# dsPIC.net
KiCad netlist of a schematic drawn in Altium Designer
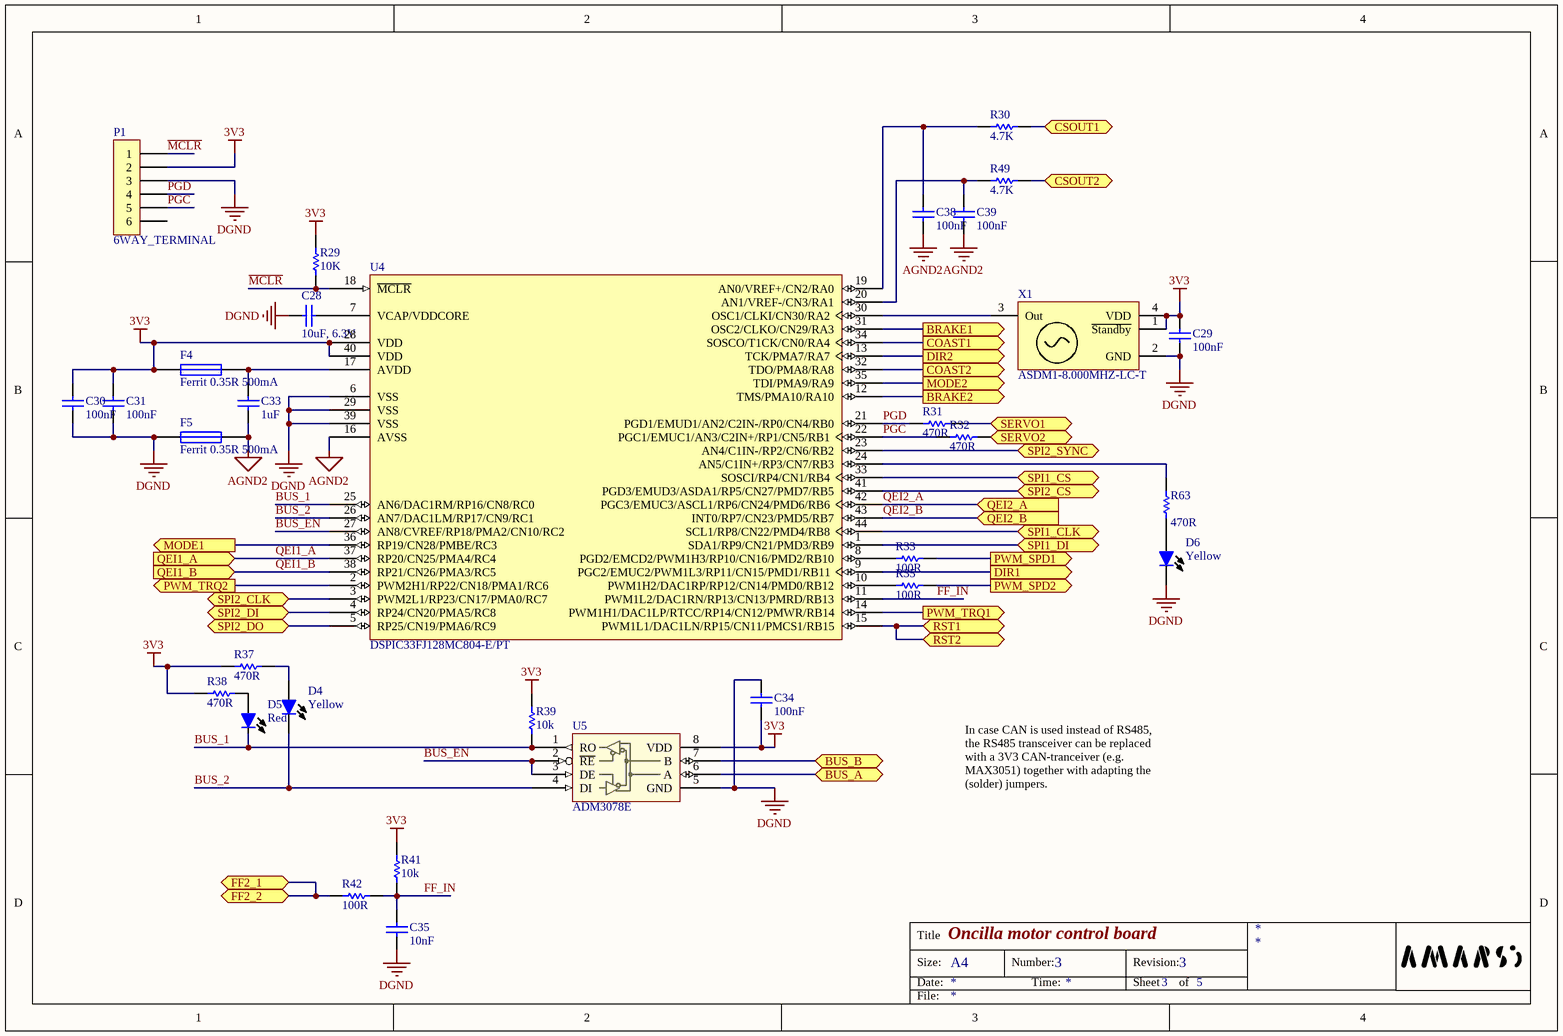
[diagram p0: dsPIC.SchDoc]

(export (version "E")
  (design (tool "Eeschema 10.0.6"))
  (components
    (comp (ref "C28")
      (value "10uF, 6.3V")
      (footprint "CAPC1608L")
      (description "Capacitor (Semiconductor SIM Model)")
      (fields (field (name "PUBLISHER") "Altium Limited"))
      (libsource (lib "Miscellaneous Devices") (part "Cap Semi"))
    )
    (comp (ref "C29")
      (value "100nF")
      (footprint "CAPC1608L")
      (description "Capacitor (Semiconductor SIM Model)")
      (fields (field (name "PUBLISHER") "Altium Limited"))
      (libsource (lib "Miscellaneous Devices") (part "Cap Semi"))
    )
    (comp (ref "C30")
      (value "100nF")
      (footprint "CAPC1608L")
      (description "Capacitor (Semiconductor SIM Model)")
      (fields (field (name "PUBLISHER") "Altium Limited"))
      (libsource (lib "Miscellaneous Devices") (part "Cap Semi"))
    )
    (comp (ref "C31")
      (value "100nF")
      (footprint "CAPC1608L")
      (description "Capacitor (Semiconductor SIM Model)")
      (fields (field (name "PUBLISHER") "Altium Limited"))
      (libsource (lib "Miscellaneous Devices") (part "Cap Semi"))
    )
    (comp (ref "C33")
      (value "1uF")
      (footprint "CAPC1608L")
      (description "Capacitor (Semiconductor SIM Model)")
      (fields (field (name "Comment") "1uF, 25V") (field (name "PUBLISHER") "Altium Limited"))
      (libsource (lib "Miscellaneous Devices") (part "Cap Semi"))
    )
    (comp (ref "C34")
      (value "100nF")
      (footprint "CAPC1608L")
      (description "Capacitor (Semiconductor SIM Model)")
      (fields (field (name "PUBLISHER") "Altium Limited"))
      (libsource (lib "Miscellaneous Devices") (part "Cap Semi"))
    )
    (comp (ref "C35")
      (value "10nF")
      (footprint "CAPC1608L")
      (description "Capacitor (Semiconductor SIM Model)")
      (fields (field (name "PUBLISHER") "Altium Limited"))
      (libsource (lib "Miscellaneous Devices") (part "Cap Semi"))
    )
    (comp (ref "C38")
      (value "100nF")
      (footprint "CAPC1608L")
      (description "Capacitor (Semiconductor SIM Model)")
      (fields (field (name "PUBLISHER") "Altium Limited"))
      (libsource (lib "Miscellaneous Devices") (part "Cap Semi"))
    )
    (comp (ref "C39")
      (value "100nF")
      (footprint "CAPC1608L")
      (description "Capacitor (Semiconductor SIM Model)")
      (fields (field (name "PUBLISHER") "Altium Limited"))
      (libsource (lib "Miscellaneous Devices") (part "Cap Semi"))
    )
    (comp (ref "D4")
      (value "LED Yellow")
      (footprint "CD1608-0603")
      (description "LED")
      (fields (field (name "COLOR") "Yellow"))
      (libsource (lib "Roombots") (part "LED"))
    )
    (comp (ref "D5")
      (value "LED Red")
      (footprint "CD1608-0603")
      (description "LED")
      (fields (field (name "COLOR") "Red"))
      (libsource (lib "Roombots") (part "LED"))
    )
    (comp (ref "D6")
      (value "LED Green")
      (footprint "CD1608-0603")
      (description "LED")
      (fields (field (name "COLOR") "Yellow"))
      (libsource (lib "Roombots") (part "LED"))
    )
    (comp (ref "F4")
      (value "Ferrit 0.35R 500mA")
      (footprint "RESC1608L")
      (description "Ferrit Bead")
      (fields (field (name "PUBLISHER") "Altium Limited"))
      (libsource (lib "Miscellaneous Devices") (part "Fuse 1"))
    )
    (comp (ref "F5")
      (value "Ferrit 0.35R 500mA")
      (footprint "RESC1608L")
      (description "Ferrit Bead")
      (fields (field (name "PUBLISHER") "Altium Limited"))
      (libsource (lib "Miscellaneous Devices") (part "Fuse 1"))
    )
    (comp (ref "P1")
      (value "6WAY_TERMINAL")
      (footprint "MICROMATCH_6WAY_SE")
      (libsource (lib "New_library") (part "6WAY_TERMINAL"))
    )
    (comp (ref "R29")
      (value "10K")
      (footprint "RESC1608L")
      (description "Semiconductor Resistor")
      (fields (field (name "Comment") "10k") (field (name "PUBLISHER") "Altium Limited"))
      (libsource (lib "Miscellaneous Devices") (part "Res Semi"))
    )
    (comp (ref "R30")
      (value "4.7K")
      (footprint "RESC1608L")
      (description "Semiconductor Resistor")
      (fields (field (name "Comment") "4.7k") (field (name "PUBLISHER") "Altium Limited"))
      (libsource (lib "Miscellaneous Devices") (part "Res Semi"))
    )
    (comp (ref "R31")
      (value "470R")
      (footprint "RESC1608L")
      (description "Semiconductor Resistor")
      (fields (field (name "PUBLISHER") "Altium Limited"))
      (libsource (lib "Miscellaneous Devices") (part "Res Semi"))
    )
    (comp (ref "R32")
      (value "470R")
      (footprint "RESC1608L")
      (description "Semiconductor Resistor")
      (fields (field (name "PUBLISHER") "Altium Limited"))
      (libsource (lib "Miscellaneous Devices") (part "Res Semi"))
    )
    (comp (ref "R33")
      (value "100R")
      (footprint "RESC1608L")
      (description "Semiconductor Resistor")
      (fields (field (name "PUBLISHER") "Altium Limited"))
      (libsource (lib "Miscellaneous Devices") (part "Res Semi"))
    )
    (comp (ref "R35")
      (value "100R")
      (footprint "RESC1608L")
      (description "Semiconductor Resistor")
      (fields (field (name "PUBLISHER") "Altium Limited"))
      (libsource (lib "Miscellaneous Devices") (part "Res Semi"))
    )
    (comp (ref "R37")
      (value "470R")
      (footprint "RESC1608L")
      (description "Semiconductor Resistor")
      (fields (field (name "PUBLISHER") "Altium Limited"))
      (libsource (lib "Miscellaneous Devices") (part "Res Semi"))
    )
    (comp (ref "R38")
      (value "470R")
      (footprint "RESC1608L")
      (description "Semiconductor Resistor")
      (fields (field (name "PUBLISHER") "Altium Limited"))
      (libsource (lib "Miscellaneous Devices") (part "Res Semi"))
    )
    (comp (ref "R39")
      (value "10k")
      (footprint "RESC1608L")
      (description "Semiconductor Resistor")
      (fields (field (name "PUBLISHER") "Altium Limited"))
      (libsource (lib "Miscellaneous Devices") (part "Res Semi"))
    )
    (comp (ref "R41")
      (value "10k")
      (footprint "RESC1608L")
      (description "Semiconductor Resistor")
      (fields (field (name "PUBLISHER") "Altium Limited"))
      (libsource (lib "Miscellaneous Devices") (part "Res Semi"))
    )
    (comp (ref "R42")
      (value "100R")
      (footprint "RESC1608L")
      (description "Semiconductor Resistor")
      (fields (field (name "PUBLISHER") "Altium Limited"))
      (libsource (lib "Miscellaneous Devices") (part "Res Semi"))
    )
    (comp (ref "R49")
      (value "4.7K")
      (footprint "RESC1608L")
      (description "Semiconductor Resistor")
      (fields (field (name "Comment") "4.7k") (field (name "PUBLISHER") "Altium Limited"))
      (libsource (lib "Miscellaneous Devices") (part "Res Semi"))
    )
    (comp (ref "R63")
      (value "470R")
      (footprint "RESC1608L")
      (description "Semiconductor Resistor")
      (fields (field (name "PUBLISHER") "Altium Limited"))
      (libsource (lib "Miscellaneous Devices") (part "Res Semi"))
    )
    (comp (ref "U4")
      (value "DSPIC33FJ128MC804-E/PT")
      (footprint "TQFP-PT44_N")
      (fields (field (name "PUBLISHER") "Altium Limited"))
      (libsource (lib "Microchip DSC 16-Bit dsPIC33F") (part "DSPIC33FJ128MC804-E/PT"))
    )
    (comp (ref "U5")
      (value "ADM3078E")
      (footprint "SOIC-8_M")
      (description "Half-Duplex RS485 Transciever, 3.3V, 16Mbps")
      (libsource (lib "Roombots") (part "ADM3078E"))
    )
    (comp (ref "X1")
      (value "ASDM1-8.000MHZ-LC-T")
      (footprint "Crystal-Oscillator-2520")
      (description "Oscillator")
      (libsource (lib "Roombots") (part "Oscillator"))
    )
  )
  (nets
    (net (code "1") (name "/BRAKE1") (class "Default")
      (node (ref "U4") (pin "31") (pinfunction "OSC2/CLKO/CN29/RA3_31") (pintype "bidirectional"))
    )
    (net (code "2") (name "/BRAKE2") (class "Default")
      (node (ref "U4") (pin "12") (pinfunction "TMS/PMA10/RA10_12") (pintype "bidirectional"))
    )
    (net (code "3") (name "/BUS_1") (class "Default")
      (node (ref "D5") (pin "2") (pinfunction "C_2") (pintype "passive"))
      (node (ref "R39") (pin "1") (pinfunction "1_1") (pintype "passive"))
      (node (ref "U4") (pin "25") (pinfunction "AN6/DAC1RM/RP16/CN8/RC0_25") (pintype "bidirectional"))
      (node (ref "U5") (pin "1") (pinfunction "RO_1") (pintype "output"))
    )
    (net (code "4") (name "/BUS_2") (class "Default")
      (node (ref "D4") (pin "2") (pinfunction "C_2") (pintype "passive"))
      (node (ref "U4") (pin "26") (pinfunction "AN7/DAC1LM/RP17/CN9/RC1_26") (pintype "bidirectional"))
      (node (ref "U5") (pin "4") (pinfunction "DI_4") (pintype "input"))
    )
    (net (code "5") (name "/BUS_A") (class "Default")
      (node (ref "U5") (pin "6") (pinfunction "A_6") (pintype "bidirectional"))
    )
    (net (code "6") (name "/BUS_B") (class "Default")
      (node (ref "U5") (pin "7") (pinfunction "B_7") (pintype "bidirectional"))
    )
    (net (code "7") (name "/BUS_EN") (class "Default")
      (node (ref "U4") (pin "27") (pinfunction "AN8/CVREF/RP18/PMA2/CN10/RC2_27") (pintype "bidirectional"))
      (node (ref "U5") (pin "2") (pinfunction "~{RE}_2") (pintype "input"))
      (node (ref "U5") (pin "3") (pinfunction "DE_3") (pintype "input"))
    )
    (net (code "8") (name "/COAST1") (class "Default")
      (node (ref "U4") (pin "34") (pinfunction "SOSCO/T1CK/CN0/RA4_34") (pintype "bidirectional"))
    )
    (net (code "9") (name "/COAST2") (class "Default")
      (node (ref "U4") (pin "32") (pinfunction "TDO/PMA8/RA8_32") (pintype "bidirectional"))
    )
    (net (code "10") (name "/CSOUT1") (class "Default")
      (node (ref "R30") (pin "2") (pinfunction "2_2") (pintype "passive"))
    )
    (net (code "11") (name "/CSOUT2") (class "Default")
      (node (ref "R49") (pin "2") (pinfunction "2_2") (pintype "passive"))
    )
    (net (code "12") (name "/DIR1") (class "Default")
      (node (ref "U4") (pin "9") (pinfunction "PGC2/EMUC2/PWM1L3/RP11/CN15/PMD1/RB11_9") (pintype "bidirectional"))
    )
    (net (code "13") (name "/DIR2") (class "Default")
      (node (ref "U4") (pin "13") (pinfunction "TCK/PMA7/RA7_13") (pintype "bidirectional"))
    )
    (net (code "14") (name "/FF2_1") (class "Default")
      (node (ref "R42") (pin "2") (pinfunction "2_2") (pintype "passive"))
    )
    (net (code "15") (name "/FF_IN") (class "Default")
      (node (ref "C35") (pin "2") (pinfunction "2_2") (pintype "passive"))
      (node (ref "R41") (pin "1") (pinfunction "1_1") (pintype "passive"))
      (node (ref "R42") (pin "1") (pinfunction "1_1") (pintype "passive"))
      (node (ref "U4") (pin "11") (pinfunction "PWM1L2/DAC1RN/RP13/CN13/PMRD/RB13_11") (pintype "bidirectional"))
    )
    (net (code "16") (name "/MODE1") (class "Default")
      (node (ref "U4") (pin "36") (pinfunction "RP19/CN28/PMBE/RC3_36") (pintype "bidirectional"))
    )
    (net (code "17") (name "/MODE2") (class "Default")
      (node (ref "U4") (pin "35") (pinfunction "TDI/PMA9/RA9_35") (pintype "bidirectional"))
    )
    (net (code "18") (name "/PGC") (class "Default")
      (node (ref "P1") (pin "5") (pinfunction "5_5") (pintype "passive"))
      (node (ref "R32") (pin "1") (pinfunction "1_1") (pintype "passive"))
      (node (ref "U4") (pin "22") (pinfunction "PGC1/EMUC1/AN3/C2IN+/RP1/CN5/RB1_22") (pintype "bidirectional"))
    )
    (net (code "19") (name "/PGD") (class "Default")
      (node (ref "P1") (pin "4") (pinfunction "4_4") (pintype "passive"))
      (node (ref "R31") (pin "1") (pinfunction "1_1") (pintype "passive"))
      (node (ref "U4") (pin "21") (pinfunction "PGD1/EMUD1/AN2/C2IN-/RP0/CN4/RB0_21") (pintype "bidirectional"))
    )
    (net (code "20") (name "/PWM_SPD1") (class "Default")
      (node (ref "R33") (pin "2") (pinfunction "2_2") (pintype "passive"))
    )
    (net (code "21") (name "/PWM_SPD2") (class "Default")
      (node (ref "R35") (pin "2") (pinfunction "2_2") (pintype "passive"))
    )
    (net (code "22") (name "/PWM_TRQ1") (class "Default")
      (node (ref "U4") (pin "14") (pinfunction "PWM1H1/DAC1LP/RTCC/RP14/CN12/PMWR/RB14_14") (pintype "bidirectional"))
    )
    (net (code "23") (name "/PWM_TRQ2") (class "Default")
      (node (ref "U4") (pin "2") (pinfunction "PWM2H1/RP22/CN18/PMA1/RC6_2") (pintype "bidirectional"))
    )
    (net (code "24") (name "/QEI1_A") (class "Default")
      (node (ref "U4") (pin "37") (pinfunction "RP20/CN25/PMA4/RC4_37") (pintype "bidirectional"))
    )
    (net (code "25") (name "/QEI1_B") (class "Default")
      (node (ref "U4") (pin "38") (pinfunction "RP21/CN26/PMA3/RC5_38") (pintype "bidirectional"))
    )
    (net (code "26") (name "/QEI2_A") (class "Default")
      (node (ref "U4") (pin "42") (pinfunction "PGC3/EMUC3/ASCL1/RP6/CN24/PMD6/RB6_42") (pintype "bidirectional"))
    )
    (net (code "27") (name "/QEI2_B") (class "Default")
      (node (ref "U4") (pin "43") (pinfunction "INT0/RP7/CN23/PMD5/RB7_43") (pintype "bidirectional"))
    )
    (net (code "28") (name "/RST1") (class "Default")
      (node (ref "U4") (pin "15") (pinfunction "PWM1L1/DAC1LN/RP15/CN11/PMCS1/RB15_15") (pintype "bidirectional"))
    )
    (net (code "29") (name "/SERVO1") (class "Default")
      (node (ref "R31") (pin "2") (pinfunction "2_2") (pintype "passive"))
    )
    (net (code "30") (name "/SERVO2") (class "Default")
      (node (ref "R32") (pin "2") (pinfunction "2_2") (pintype "passive"))
    )
    (net (code "31") (name "/SPI1_CLK") (class "Default")
      (node (ref "U4") (pin "44") (pinfunction "SCL1/RP8/CN22/PMD4/RB8_44") (pintype "bidirectional"))
    )
    (net (code "32") (name "/SPI1_CS") (class "Default")
      (node (ref "U4") (pin "33") (pinfunction "SOSCI/RP4/CN1/RB4_33") (pintype "bidirectional"))
    )
    (net (code "33") (name "/SPI1_DI") (class "Default")
      (node (ref "U4") (pin "1") (pinfunction "SDA1/RP9/CN21/PMD3/RB9_1") (pintype "bidirectional"))
    )
    (net (code "34") (name "/SPI2_CLK") (class "Default")
      (node (ref "U4") (pin "3") (pinfunction "PWM2L1/RP23/CN17/PMA0/RC7_3") (pintype "bidirectional"))
    )
    (net (code "35") (name "/SPI2_CS") (class "Default")
      (node (ref "U4") (pin "41") (pinfunction "PGD3/EMUD3/ASDA1/RP5/CN27/PMD7/RB5_41") (pintype "bidirectional"))
    )
    (net (code "36") (name "/SPI2_DI") (class "Default")
      (node (ref "U4") (pin "4") (pinfunction "RP24/CN20/PMA5/RC8_4") (pintype "bidirectional"))
    )
    (net (code "37") (name "/SPI2_DO") (class "Default")
      (node (ref "U4") (pin "5") (pinfunction "RP25/CN19/PMA6/RC9_5") (pintype "bidirectional"))
    )
    (net (code "38") (name "/SPI2_SYNC") (class "Default")
      (node (ref "U4") (pin "23") (pinfunction "AN4/C1IN-/RP2/CN6/RB2_23") (pintype "bidirectional"))
    )
    (net (code "39") (name "/~{MCLR}") (class "Default")
      (node (ref "P1") (pin "1") (pinfunction "1_1") (pintype "passive"))
      (node (ref "R29") (pin "1") (pinfunction "1_1") (pintype "passive"))
      (node (ref "U4") (pin "18") (pinfunction "~{MCLR}_18") (pintype "input"))
    )
    (net (code "40") (name "3V3") (class "Default")
      (node (ref "C29") (pin "2") (pinfunction "2_2") (pintype "passive"))
      (node (ref "C30") (pin "2") (pinfunction "2_2") (pintype "passive"))
      (node (ref "C31") (pin "2") (pinfunction "2_2") (pintype "passive"))
      (node (ref "C34") (pin "1") (pinfunction "1_1") (pintype "passive"))
      (node (ref "F4") (pin "1") (pinfunction "1_1") (pintype "passive"))
      (node (ref "P1") (pin "2") (pinfunction "2_2") (pintype "passive"))
      (node (ref "R29") (pin "2") (pinfunction "2_2") (pintype "passive"))
      (node (ref "R37") (pin "1") (pinfunction "1_1") (pintype "passive"))
      (node (ref "R38") (pin "1") (pinfunction "1_1") (pintype "passive"))
      (node (ref "R39") (pin "2") (pinfunction "2_2") (pintype "passive"))
      (node (ref "R41") (pin "2") (pinfunction "2_2") (pintype "passive"))
      (node (ref "U4") (pin "28") (pinfunction "VDD_28") (pintype "power_in"))
      (node (ref "U4") (pin "40") (pinfunction "VDD_40") (pintype "power_in"))
      (node (ref "U5") (pin "8") (pinfunction "VDD_8") (pintype "power_in"))
      (node (ref "X1") (pin "1") (pinfunction "~{Standby}_1") (pintype "passive"))
      (node (ref "X1") (pin "4") (pinfunction "VDD_4") (pintype "passive"))
    )
    (net (code "41") (name "AGND2") (class "Default")
      (node (ref "C33") (pin "1") (pinfunction "1_1") (pintype "passive"))
      (node (ref "C38") (pin "1") (pinfunction "1_1") (pintype "passive"))
      (node (ref "C39") (pin "1") (pinfunction "1_1") (pintype "passive"))
      (node (ref "F5") (pin "2") (pinfunction "2_2") (pintype "passive"))
      (node (ref "U4") (pin "16") (pinfunction "AVSS_16") (pintype "power_in"))
    )
    (net (code "42") (name "DGND") (class "Default")
      (node (ref "C28") (pin "1") (pinfunction "1_1") (pintype "passive"))
      (node (ref "C29") (pin "1") (pinfunction "1_1") (pintype "passive"))
      (node (ref "C30") (pin "1") (pinfunction "1_1") (pintype "passive"))
      (node (ref "C31") (pin "1") (pinfunction "1_1") (pintype "passive"))
      (node (ref "C34") (pin "2") (pinfunction "2_2") (pintype "passive"))
      (node (ref "C35") (pin "1") (pinfunction "1_1") (pintype "passive"))
      (node (ref "D6") (pin "2") (pinfunction "C_2") (pintype "passive"))
      (node (ref "F5") (pin "1") (pinfunction "1_1") (pintype "passive"))
      (node (ref "P1") (pin "3") (pinfunction "3_3") (pintype "passive"))
      (node (ref "U4") (pin "29") (pinfunction "VSS_29") (pintype "power_in"))
      (node (ref "U4") (pin "39") (pinfunction "VSS_39") (pintype "power_in"))
      (node (ref "U4") (pin "6") (pinfunction "VSS_6") (pintype "power_in"))
      (node (ref "U5") (pin "5") (pinfunction "GND_5") (pintype "power_in"))
      (node (ref "X1") (pin "2") (pinfunction "GND_2") (pintype "passive"))
    )
    (net (code "43") (name "Net-(D4-A)") (class "Default")
      (node (ref "D4") (pin "1") (pinfunction "A_1") (pintype "passive"))
      (node (ref "R37") (pin "2") (pinfunction "2_2") (pintype "passive"))
    )
    (net (code "44") (name "Net-(D5-A)") (class "Default")
      (node (ref "D5") (pin "1") (pinfunction "A_1") (pintype "passive"))
      (node (ref "R38") (pin "2") (pinfunction "2_2") (pintype "passive"))
    )
    (net (code "45") (name "Net-(D6-A)") (class "Default")
      (node (ref "D6") (pin "1") (pinfunction "A_1") (pintype "passive"))
      (node (ref "R63") (pin "1") (pinfunction "1_1") (pintype "passive"))
    )
    (net (code "46") (name "Net-(U4-AN0{slash}VREF+{slash}CN2{slash}RA0)") (class "Default")
      (node (ref "C38") (pin "2") (pinfunction "2_2") (pintype "passive"))
      (node (ref "R30") (pin "1") (pinfunction "1_1") (pintype "passive"))
      (node (ref "U4") (pin "19") (pinfunction "AN0/VREF+/CN2/RA0_19") (pintype "bidirectional"))
    )
    (net (code "47") (name "Net-(U4-AN1{slash}VREF-{slash}CN3{slash}RA1)") (class "Default")
      (node (ref "C39") (pin "2") (pinfunction "2_2") (pintype "passive"))
      (node (ref "R49") (pin "1") (pinfunction "1_1") (pintype "passive"))
      (node (ref "U4") (pin "20") (pinfunction "AN1/VREF-/CN3/RA1_20") (pintype "bidirectional"))
    )
    (net (code "48") (name "Net-(U4-AN5{slash}C1IN+{slash}RP3{slash}CN7{slash}RB3)") (class "Default")
      (node (ref "R63") (pin "2") (pinfunction "2_2") (pintype "passive"))
      (node (ref "U4") (pin "24") (pinfunction "AN5/C1IN+/RP3/CN7/RB3_24") (pintype "bidirectional"))
    )
    (net (code "49") (name "Net-(U4-AVDD)") (class "Default")
      (node (ref "C33") (pin "2") (pinfunction "2_2") (pintype "passive"))
      (node (ref "F4") (pin "2") (pinfunction "2_2") (pintype "passive"))
      (node (ref "U4") (pin "17") (pinfunction "AVDD_17") (pintype "power_in"))
    )
    (net (code "50") (name "Net-(U4-OSC1{slash}CLKI{slash}CN30{slash}RA2)") (class "Default")
      (node (ref "U4") (pin "30") (pinfunction "OSC1/CLKI/CN30/RA2_30") (pintype "bidirectional"))
      (node (ref "X1") (pin "3") (pinfunction "Out_3") (pintype "passive"))
    )
    (net (code "51") (name "Net-(U4-PGD2{slash}EMCD2{slash}PWM1H3{slash}RP10{slash}CN16{slash}PMD2{slash}RB10)") (class "Default")
      (node (ref "R33") (pin "1") (pinfunction "1_1") (pintype "passive"))
      (node (ref "U4") (pin "8") (pinfunction "PGD2/EMCD2/PWM1H3/RP10/CN16/PMD2/RB10_8") (pintype "bidirectional"))
    )
    (net (code "52") (name "Net-(U4-PWM1H2{slash}DAC1RP{slash}RP12{slash}CN14{slash}PMD0{slash}RB12)") (class "Default")
      (node (ref "R35") (pin "1") (pinfunction "1_1") (pintype "passive"))
      (node (ref "U4") (pin "10") (pinfunction "PWM1H2/DAC1RP/RP12/CN14/PMD0/RB12_10") (pintype "bidirectional"))
    )
    (net (code "53") (name "Net-(U4-VCAP{slash}VDDCORE)") (class "Default")
      (node (ref "C28") (pin "2") (pinfunction "2_2") (pintype "passive"))
      (node (ref "U4") (pin "7") (pinfunction "VCAP/VDDCORE_7") (pintype "power_in"))
    )
    (net (code "54") (name "unconnected-(P1-Pad6)") (class "Default")
      (node (ref "P1") (pin "6") (pinfunction "6_6") (pintype "passive"))
    )
  )
)
